# Wi-Fi.net
KiCad netlist of a schematic drawn in Altium Designer
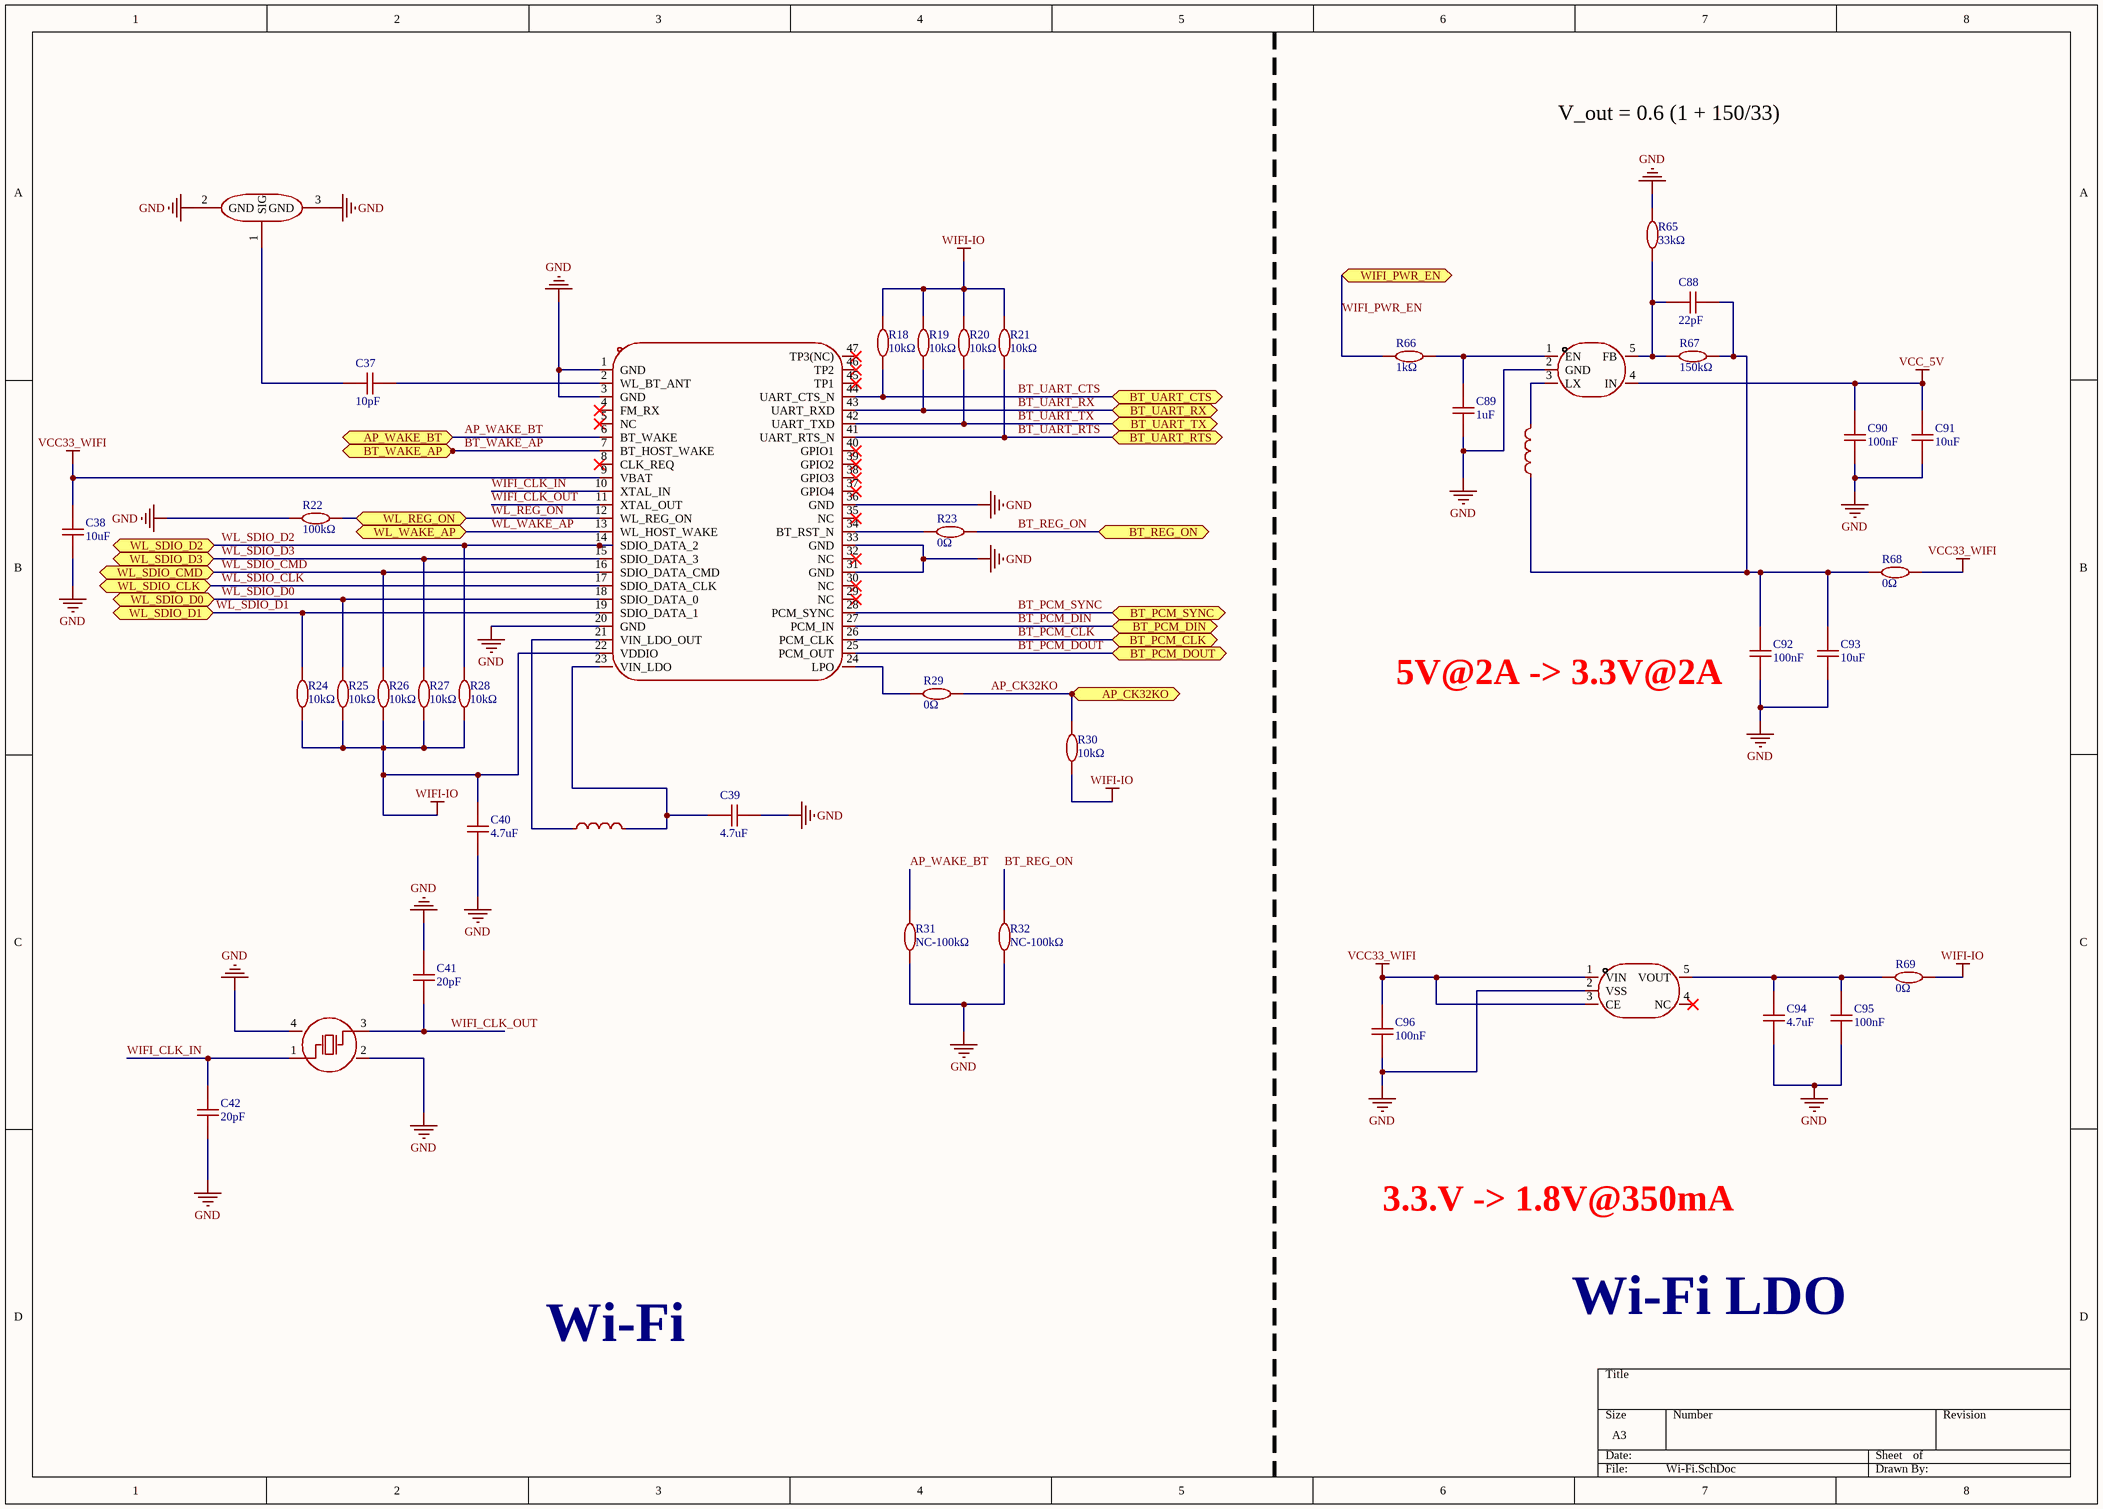
[diagram p0: Wi-Fi.SchDoc]

(export (version "E")
  (design (tool "Eeschema 10.0.6"))
  (components
    (comp (ref "C37")
      (value "10pF")
      (footprint "C0402")
      (description "50V 10pF C0G ±5% 0402 Ceramic Capacitors ROHS")
      (libsource (lib "RLC") (part "10pF"))
    )
    (comp (ref "C38")
      (value "10uF")
      (footprint "C0603")
      (description "10V 10uF X5R ±10% 0603 Ceramic Capacitors ROHS")
      (libsource (lib "RLC") (part "10uF"))
    )
    (comp (ref "C39")
      (value "4.7uF")
      (footprint "C0402")
      (description "10V 4.7uF X5R ±20% 0402 Ceramic Capacitors ROHS")
      (libsource (lib "RLC") (part "4.7uF"))
    )
    (comp (ref "C40")
      (value "4.7uF")
      (footprint "C0402")
      (description "10V 4.7uF X5R ±20% 0402 Ceramic Capacitors ROHS")
      (libsource (lib "RLC") (part "4.7uF"))
    )
    (comp (ref "C41")
      (value "20pF")
      (footprint "C0402")
      (description "50V 20pF NP0 ±5% 0402 Ceramic Capacitors ROHS")
      (libsource (lib "RLC") (part "20pF"))
    )
    (comp (ref "C42")
      (value "20pF")
      (footprint "C0402")
      (description "50V 20pF NP0 ±5% 0402 Ceramic Capacitors ROHS")
      (libsource (lib "RLC") (part "20pF"))
    )
    (comp (ref "C88")
      (value "22pF")
      (footprint "C0402")
      (description "50V 22pF C0G ±5% 0402 Ceramic Capacitors ROHS")
      (libsource (lib "RLC") (part "22pF"))
    )
    (comp (ref "C89")
      (value "1uF")
      (footprint "C0402")
      (description "50V 1uF X5R ±10% 0402 Ceramic Capacitors ROHS")
      (libsource (lib "RLC") (part "1uF"))
    )
    (comp (ref "C90")
      (value "100nF")
      (footprint "C0402")
      (description "50V 100nF X7R ±10% 0402 Ceramic Capacitors ROHS")
      (libsource (lib "RLC") (part "100nF"))
    )
    (comp (ref "C91")
      (value "10uF")
      (footprint "C0603")
      (description "10V 10uF X5R ±10% 0603 Ceramic Capacitors ROHS")
      (libsource (lib "RLC") (part "10uF"))
    )
    (comp (ref "C92")
      (value "100nF")
      (footprint "C0402")
      (description "50V 100nF X7R ±10% 0402 Ceramic Capacitors ROHS")
      (libsource (lib "RLC") (part "100nF"))
    )
    (comp (ref "C93")
      (value "10uF")
      (footprint "C0603")
      (description "10V 10uF X5R ±10% 0603 Ceramic Capacitors ROHS")
      (libsource (lib "RLC") (part "10uF"))
    )
    (comp (ref "C94")
      (value "4.7uF")
      (footprint "C0402")
      (description "10V 4.7uF X5R ±20% 0402 Ceramic Capacitors ROHS")
      (libsource (lib "RLC") (part "4.7uF"))
    )
    (comp (ref "C95")
      (value "100nF")
      (footprint "C0402")
      (description "50V 100nF X7R ±10% 0402 Ceramic Capacitors ROHS")
      (libsource (lib "RLC") (part "100nF"))
    )
    (comp (ref "C96")
      (value "100nF")
      (footprint "C0402")
      (description "50V 100nF X7R ±10% 0402 Ceramic Capacitors ROHS")
      (libsource (lib "RLC") (part "100nF"))
    )
    (comp (ref "JP1")
      (value "6GHz")
      (footprint "RF-SMD_FRF05002-JSS103M")
      (fields (field (name "MANUFACTURER") "HRS(广濑)") (field (name "MANUFACTURER PART") "U.FL-R-SMT-1(80)"))
      (libsource (lib "Connector") (part "U.FL-R-SMT-1(80)_C88374"))
    )
    (comp (ref "L1")
      (value "4.7uH")
      (footprint "IND-SMD_L6.0-W6.0_FNR60XXS")
      (description "2.5A 4.7uH Magnetic Shielded Inductor ±20% 3.6A 75mΩ SMD,6x6mm Fixed Inductors ROHS")
      (fields (field (name "MANUFACTURER") "cjiang(长江微电)") (field (name "MANUFACTURER PART") "FNR6020S4R7MT"))
      (libsource (lib "RLC") (part "FNR6020S4R7MT"))
    )
    (comp (ref "L7")
      (value "4.7uH")
      (footprint "IND-SMD_L6.0-W6.0_FNR60XXS")
      (description "2.5A 4.7uH Magnetic Shielded Inductor ±20% 3.6A 75mΩ SMD,6x6mm Fixed Inductors ROHS")
      (fields (field (name "MANUFACTURER") "cjiang(长江微电)") (field (name "MANUFACTURER PART") "FNR6020S4R7MT"))
      (libsource (lib "RLC") (part "FNR6020S4R7MT"))
    )
    (comp (ref "R18")
      (value "10kΩ")
      (footprint "R0402")
      (description "62.5mW 10kΩ 50V ±100ppm/℃ Thick Film Resistor ±1% 0402 Chip Resistor - Surface Mount ROHS")
      (libsource (lib "RLC") (part "10kΩ"))
    )
    (comp (ref "R19")
      (value "10kΩ")
      (footprint "R0402")
      (description "62.5mW 10kΩ 50V ±100ppm/℃ Thick Film Resistor ±1% 0402 Chip Resistor - Surface Mount ROHS")
      (libsource (lib "RLC") (part "10kΩ"))
    )
    (comp (ref "R20")
      (value "10kΩ")
      (footprint "R0402")
      (description "62.5mW 10kΩ 50V ±100ppm/℃ Thick Film Resistor ±1% 0402 Chip Resistor - Surface Mount ROHS")
      (libsource (lib "RLC") (part "10kΩ"))
    )
    (comp (ref "R21")
      (value "10kΩ")
      (footprint "R0402")
      (description "62.5mW 10kΩ 50V ±100ppm/℃ Thick Film Resistor ±1% 0402 Chip Resistor - Surface Mount ROHS")
      (libsource (lib "RLC") (part "10kΩ"))
    )
    (comp (ref "R22")
      (value "100kΩ")
      (footprint "R0402")
      (description "100kΩ 62.5mW 50V ±100ppm/℃ Thick Film Resistor ±1% 0402 Chip Resistor - Surface Mount ROHS")
      (libsource (lib "RLC") (part "100kΩ"))
    )
    (comp (ref "R23")
      (value "0Ω")
      (footprint "R0402")
      (description "0Ω 62.5mW 50V Thick Film Resistor ±1% 0402 Chip Resistor - Surface Mount ROHS")
      (libsource (lib "RLC") (part "0Ω"))
    )
    (comp (ref "R24")
      (value "10kΩ")
      (footprint "R0402")
      (description "62.5mW 10kΩ 50V ±100ppm/℃ Thick Film Resistor ±1% 0402 Chip Resistor - Surface Mount ROHS")
      (libsource (lib "RLC") (part "10kΩ"))
    )
    (comp (ref "R25")
      (value "10kΩ")
      (footprint "R0402")
      (description "62.5mW 10kΩ 50V ±100ppm/℃ Thick Film Resistor ±1% 0402 Chip Resistor - Surface Mount ROHS")
      (libsource (lib "RLC") (part "10kΩ"))
    )
    (comp (ref "R26")
      (value "10kΩ")
      (footprint "R0402")
      (description "62.5mW 10kΩ 50V ±100ppm/℃ Thick Film Resistor ±1% 0402 Chip Resistor - Surface Mount ROHS")
      (libsource (lib "RLC") (part "10kΩ"))
    )
    (comp (ref "R27")
      (value "10kΩ")
      (footprint "R0402")
      (description "62.5mW 10kΩ 50V ±100ppm/℃ Thick Film Resistor ±1% 0402 Chip Resistor - Surface Mount ROHS")
      (libsource (lib "RLC") (part "10kΩ"))
    )
    (comp (ref "R28")
      (value "10kΩ")
      (footprint "R0402")
      (description "62.5mW 10kΩ 50V ±100ppm/℃ Thick Film Resistor ±1% 0402 Chip Resistor - Surface Mount ROHS")
      (libsource (lib "RLC") (part "10kΩ"))
    )
    (comp (ref "R29")
      (value "0Ω")
      (footprint "R0402")
      (description "0Ω 62.5mW 50V Thick Film Resistor ±1% 0402 Chip Resistor - Surface Mount ROHS")
      (libsource (lib "RLC") (part "0Ω"))
    )
    (comp (ref "R30")
      (value "10kΩ")
      (footprint "R0402")
      (description "62.5mW 10kΩ 50V ±100ppm/℃ Thick Film Resistor ±1% 0402 Chip Resistor - Surface Mount ROHS")
      (libsource (lib "RLC") (part "10kΩ"))
    )
    (comp (ref "R31")
      (value "NC-100kΩ")
      (footprint "R0402")
      (description "100kΩ 62.5mW 50V ±100ppm/℃ Thick Film Resistor ±1% 0402 Chip Resistor - Surface Mount ROHS")
      (libsource (lib "RLC") (part "100kΩ"))
    )
    (comp (ref "R32")
      (value "NC-100kΩ")
      (footprint "R0402")
      (description "100kΩ 62.5mW 50V ±100ppm/℃ Thick Film Resistor ±1% 0402 Chip Resistor - Surface Mount ROHS")
      (libsource (lib "RLC") (part "100kΩ"))
    )
    (comp (ref "R65")
      (value "33kΩ")
      (footprint "R0402")
      (description "62.5mW 33kΩ 50V ±100ppm/℃ Thick Film Resistor ±1% 0402 Chip Resistor - Surface Mount ROHS")
      (libsource (lib "RLC") (part "33kΩ"))
    )
    (comp (ref "R66")
      (value "1kΩ")
      (footprint "R0402")
      (description "1kΩ 62.5mW 50V ±100ppm/℃ Thick Film Resistor ±1% 0402 Chip Resistor - Surface Mount ROHS")
      (libsource (lib "RLC") (part "1kΩ"))
    )
    (comp (ref "R67")
      (value "150kΩ")
      (footprint "R0402")
      (description "62.5mW 150kΩ 50V ±100ppm/℃ Thick Film Resistor ±1% 0402 Chip Resistor - Surface Mount ROHS")
      (libsource (lib "RLC") (part "150kΩ"))
    )
    (comp (ref "R68")
      (value "0Ω")
      (footprint "R0402")
      (description "0Ω 62.5mW 50V Thick Film Resistor ±1% 0402 Chip Resistor - Surface Mount ROHS")
      (libsource (lib "RLC") (part "0Ω"))
    )
    (comp (ref "R69")
      (value "0Ω")
      (footprint "R0402")
      (description "0Ω 62.5mW 50V Thick Film Resistor ±1% 0402 Chip Resistor - Surface Mount ROHS")
      (libsource (lib "RLC") (part "0Ω"))
    )
    (comp (ref "U6")
      (value "2.4GHz")
      (footprint "QFN-44_L12.0-W12.0-P0.90-TL_AP6212")
      (description "2.4GHz -90dBm QFN-44(12x12) RF Transceiver Modules and Modems ROHS")
      (fields (field (name "MANUFACTURER") "AMPAK(正基科技)") (field (name "MANUFACTURER PART") "AP6212"))
      (libsource (lib "IC") (part "AP6212"))
    )
    (comp (ref "U30")
      (value "SY8089A1AAC")
      (footprint "TSOT-23-5_L2.9-W1.6-P0.95-LS2.8-BR")
      (description "1.5MHz Buck 2A Adjustable 1 SOT-23-5 Voltage Regulators - DC DC Switching Regulators ROHS")
      (fields (field (name "MANUFACTURER") "Silergy(矽力杰)"))
      (libsource (lib "LDO") (part "SY8089A1AAC"))
    )
    (comp (ref "U31")
      (value "ME6212C18M5G")
      (footprint "SOT-23-5_L3.0-W1.7-P0.95-LS2.8-BL")
      (fields (field (name "MANUFACTURER") "MICRONE(南京微盟)"))
      (libsource (lib "LDO") (part "ME6212C18M5G"))
    )
    (comp (ref "X1")
      (value "26MHz")
      (footprint "CRYSTAL-SMD_4P-L3.2-W2.5-BL")
      (description "Crystal Oscillator 20pF SMD3225-4P Crystals ROHS")
      (fields (field (name "MANUFACTURER") "YJX(雅晶鑫)") (field (name "MANUFACTURER PART") "TAXM26M4RLBCCT2T"))
      (libsource (lib "OSC") (part "TAXM26M4RLBCCT2T"))
    )
  )
  (nets
    (net (code "1") (name "/AP_CK32KO") (class "Default")
      (node (ref "R29") (pin "2") (pinfunction "2_2") (pintype "passive"))
      (node (ref "R30") (pin "2") (pinfunction "2_2") (pintype "passive"))
    )
    (net (code "2") (name "/AP_WAKE_BT") (class "Default")
      (node (ref "R31") (pin "2") (pinfunction "2_2") (pintype "passive"))
      (node (ref "U6") (pin "6") (pinfunction "BT_WAKE_6") (pintype "passive"))
    )
    (net (code "3") (name "/BT_PCM_CLK") (class "Default")
      (node (ref "U6") (pin "26") (pinfunction "PCM_CLK_26") (pintype "passive"))
    )
    (net (code "4") (name "/BT_PCM_DIN") (class "Default")
      (node (ref "U6") (pin "27") (pinfunction "PCM_IN_27") (pintype "passive"))
    )
    (net (code "5") (name "/BT_PCM_DOUT") (class "Default")
      (node (ref "U6") (pin "25") (pinfunction "PCM_OUT_25") (pintype "passive"))
    )
    (net (code "6") (name "/BT_PCM_SYNC") (class "Default")
      (node (ref "U6") (pin "28") (pinfunction "PCM_SYNC_28") (pintype "passive"))
    )
    (net (code "7") (name "/BT_REG_ON") (class "Default")
      (node (ref "R23") (pin "2") (pinfunction "2_2") (pintype "passive"))
      (node (ref "R32") (pin "2") (pinfunction "2_2") (pintype "passive"))
    )
    (net (code "8") (name "/BT_UART_CTS") (class "Default")
      (node (ref "R18") (pin "1") (pinfunction "1_1") (pintype "passive"))
      (node (ref "U6") (pin "44") (pinfunction "UART_CTS_N_44") (pintype "passive"))
    )
    (net (code "9") (name "/BT_UART_RTS") (class "Default")
      (node (ref "R21") (pin "1") (pinfunction "1_1") (pintype "passive"))
      (node (ref "U6") (pin "41") (pinfunction "UART_RTS_N_41") (pintype "passive"))
    )
    (net (code "10") (name "/BT_UART_RX") (class "Default")
      (node (ref "R19") (pin "1") (pinfunction "1_1") (pintype "passive"))
      (node (ref "U6") (pin "43") (pinfunction "UART_RXD_43") (pintype "passive"))
    )
    (net (code "11") (name "/BT_UART_TX") (class "Default")
      (node (ref "R20") (pin "1") (pinfunction "1_1") (pintype "passive"))
      (node (ref "U6") (pin "42") (pinfunction "UART_TXD_42") (pintype "passive"))
    )
    (net (code "12") (name "/BT_WAKE_AP") (class "Default")
      (node (ref "U6") (pin "7") (pinfunction "BT_HOST_WAKE_7") (pintype "passive"))
    )
    (net (code "13") (name "/WIFI_CLK_IN") (class "Default")
      (node (ref "C42") (pin "2") (pinfunction "2_2") (pintype "passive"))
      (node (ref "U6") (pin "10") (pinfunction "XTAL_IN_10") (pintype "passive"))
      (node (ref "X1") (pin "1") (pinfunction "OSC1_1") (pintype "passive"))
    )
    (net (code "14") (name "/WIFI_CLK_OUT") (class "Default")
      (node (ref "C41") (pin "1") (pinfunction "1_1") (pintype "passive"))
      (node (ref "U6") (pin "11") (pinfunction "XTAL_OUT_11") (pintype "passive"))
      (node (ref "X1") (pin "3") (pinfunction "OSC2_3") (pintype "passive"))
    )
    (net (code "15") (name "/WIFI_PWR_EN") (class "Default")
      (node (ref "R66") (pin "1") (pinfunction "1_1") (pintype "passive"))
    )
    (net (code "16") (name "/WL_REG_ON") (class "Default")
      (node (ref "R22") (pin "2") (pinfunction "2_2") (pintype "passive"))
      (node (ref "U6") (pin "12") (pinfunction "WL_REG_ON_12") (pintype "passive"))
    )
    (net (code "17") (name "/WL_SDIO_CLK") (class "Default")
      (node (ref "U6") (pin "17") (pinfunction "SDIO_DATA_CLK_17") (pintype "passive"))
    )
    (net (code "18") (name "/WL_SDIO_CMD") (class "Default")
      (node (ref "R26") (pin "2") (pinfunction "2_2") (pintype "passive"))
      (node (ref "U6") (pin "16") (pinfunction "SDIO_DATA_CMD_16") (pintype "passive"))
    )
    (net (code "19") (name "/WL_SDIO_D0") (class "Default")
      (node (ref "R25") (pin "2") (pinfunction "2_2") (pintype "passive"))
      (node (ref "U6") (pin "18") (pinfunction "SDIO_DATA_0_18") (pintype "passive"))
    )
    (net (code "20") (name "/WL_SDIO_D1") (class "Default")
      (node (ref "R24") (pin "2") (pinfunction "2_2") (pintype "passive"))
      (node (ref "U6") (pin "19") (pinfunction "SDIO_DATA_1_19") (pintype "passive"))
    )
    (net (code "21") (name "/WL_SDIO_D2") (class "Default")
      (node (ref "R28") (pin "2") (pinfunction "2_2") (pintype "passive"))
      (node (ref "U6") (pin "14") (pinfunction "SDIO_DATA_2_14") (pintype "passive"))
    )
    (net (code "22") (name "/WL_SDIO_D3") (class "Default")
      (node (ref "R27") (pin "2") (pinfunction "2_2") (pintype "passive"))
      (node (ref "U6") (pin "15") (pinfunction "SDIO_DATA_3_15") (pintype "passive"))
    )
    (net (code "23") (name "/WL_WAKE_AP") (class "Default")
      (node (ref "U6") (pin "13") (pinfunction "WL_HOST_WAKE_13") (pintype "passive"))
    )
    (net (code "24") (name "GND") (class "Default")
      (node (ref "C38") (pin "1") (pinfunction "1_1") (pintype "passive"))
      (node (ref "C39") (pin "2") (pinfunction "2_2") (pintype "passive"))
      (node (ref "C40") (pin "1") (pinfunction "1_1") (pintype "passive"))
      (node (ref "C41") (pin "2") (pinfunction "2_2") (pintype "passive"))
      (node (ref "C42") (pin "1") (pinfunction "1_1") (pintype "passive"))
      (node (ref "C89") (pin "1") (pinfunction "1_1") (pintype "passive"))
      (node (ref "C90") (pin "1") (pinfunction "1_1") (pintype "passive"))
      (node (ref "C91") (pin "1") (pinfunction "1_1") (pintype "passive"))
      (node (ref "C92") (pin "1") (pinfunction "1_1") (pintype "passive"))
      (node (ref "C93") (pin "1") (pinfunction "1_1") (pintype "passive"))
      (node (ref "C94") (pin "1") (pinfunction "1_1") (pintype "passive"))
      (node (ref "C95") (pin "1") (pinfunction "1_1") (pintype "passive"))
      (node (ref "C96") (pin "1") (pinfunction "1_1") (pintype "passive"))
      (node (ref "JP1") (pin "2") (pinfunction "GND_2") (pintype "passive"))
      (node (ref "JP1") (pin "3") (pinfunction "GND_3") (pintype "passive"))
      (node (ref "R22") (pin "1") (pinfunction "1_1") (pintype "passive"))
      (node (ref "R31") (pin "1") (pinfunction "1_1") (pintype "passive"))
      (node (ref "R32") (pin "1") (pinfunction "1_1") (pintype "passive"))
      (node (ref "R65") (pin "2") (pinfunction "2_2") (pintype "passive"))
      (node (ref "U30") (pin "2") (pinfunction "GND_2") (pintype "passive"))
      (node (ref "U31") (pin "2") (pinfunction "VSS_2") (pintype "passive"))
      (node (ref "U6") (pin "1") (pinfunction "GND_1") (pintype "passive"))
      (node (ref "U6") (pin "20") (pinfunction "GND_20") (pintype "passive"))
      (node (ref "U6") (pin "3") (pinfunction "GND_3") (pintype "passive"))
      (node (ref "U6") (pin "31") (pinfunction "GND_31") (pintype "passive"))
      (node (ref "U6") (pin "33") (pinfunction "GND_33") (pintype "passive"))
      (node (ref "U6") (pin "36") (pinfunction "GND_36") (pintype "passive"))
      (node (ref "X1") (pin "2") (pinfunction "GND_2") (pintype "passive"))
      (node (ref "X1") (pin "4") (pinfunction "GND_4") (pintype "passive"))
    )
    (net (code "25") (name "Net-(C88-Pad2)") (class "Default")
      (node (ref "C88") (pin "2") (pinfunction "2_2") (pintype "passive"))
      (node (ref "C92") (pin "2") (pinfunction "2_2") (pintype "passive"))
      (node (ref "C93") (pin "2") (pinfunction "2_2") (pintype "passive"))
      (node (ref "L7") (pin "1") (pinfunction "1_1") (pintype "passive"))
      (node (ref "R67") (pin "2") (pinfunction "2_2") (pintype "passive"))
      (node (ref "R68") (pin "1") (pinfunction "1_1") (pintype "passive"))
    )
    (net (code "26") (name "Net-(JP1-SIG)") (class "Default")
      (node (ref "C37") (pin "1") (pinfunction "1_1") (pintype "passive"))
      (node (ref "JP1") (pin "1") (pinfunction "SIG_1") (pintype "passive"))
    )
    (net (code "27") (name "Net-(U6-BT_RST_N)") (class "Default")
      (node (ref "R23") (pin "1") (pinfunction "1_1") (pintype "passive"))
      (node (ref "U6") (pin "34") (pinfunction "BT_RST_N_34") (pintype "passive"))
    )
    (net (code "28") (name "Net-(U6-LPO)") (class "Default")
      (node (ref "R29") (pin "1") (pinfunction "1_1") (pintype "passive"))
      (node (ref "U6") (pin "24") (pinfunction "LPO_24") (pintype "passive"))
    )
    (net (code "29") (name "Net-(U6-VIN_LDO)") (class "Default")
      (node (ref "C39") (pin "1") (pinfunction "1_1") (pintype "passive"))
      (node (ref "L1") (pin "2") (pinfunction "2_2") (pintype "passive"))
      (node (ref "U6") (pin "23") (pinfunction "VIN_LDO_23") (pintype "passive"))
    )
    (net (code "30") (name "Net-(U6-VIN_LDO_OUT)") (class "Default")
      (node (ref "L1") (pin "1") (pinfunction "1_1") (pintype "passive"))
      (node (ref "U6") (pin "21") (pinfunction "VIN_LDO_OUT_21") (pintype "passive"))
    )
    (net (code "31") (name "Net-(U6-WL_BT_ANT)") (class "Default")
      (node (ref "C37") (pin "2") (pinfunction "2_2") (pintype "passive"))
      (node (ref "U6") (pin "2") (pinfunction "WL_BT_ANT_2") (pintype "passive"))
    )
    (net (code "32") (name "Net-(U30-EN)") (class "Default")
      (node (ref "C89") (pin "2") (pinfunction "2_2") (pintype "passive"))
      (node (ref "R66") (pin "2") (pinfunction "2_2") (pintype "passive"))
      (node (ref "U30") (pin "1") (pinfunction "EN_1") (pintype "passive"))
    )
    (net (code "33") (name "Net-(U30-FB)") (class "Default")
      (node (ref "C88") (pin "1") (pinfunction "1_1") (pintype "passive"))
      (node (ref "R65") (pin "1") (pinfunction "1_1") (pintype "passive"))
      (node (ref "R67") (pin "1") (pinfunction "1_1") (pintype "passive"))
      (node (ref "U30") (pin "5") (pinfunction "FB_5") (pintype "passive"))
    )
    (net (code "34") (name "Net-(U30-LX)") (class "Default")
      (node (ref "L7") (pin "2") (pinfunction "2_2") (pintype "passive"))
      (node (ref "U30") (pin "3") (pinfunction "LX_3") (pintype "passive"))
    )
    (net (code "35") (name "Net-(U31-VOUT)") (class "Default")
      (node (ref "C94") (pin "2") (pinfunction "2_2") (pintype "passive"))
      (node (ref "C95") (pin "2") (pinfunction "2_2") (pintype "passive"))
      (node (ref "R69") (pin "1") (pinfunction "1_1") (pintype "passive"))
      (node (ref "U31") (pin "5") (pinfunction "VOUT_5") (pintype "passive"))
    )
    (net (code "36") (name "VCC33_WIFI") (class "Default")
      (node (ref "C38") (pin "2") (pinfunction "2_2") (pintype "passive"))
      (node (ref "C96") (pin "2") (pinfunction "2_2") (pintype "passive"))
      (node (ref "R68") (pin "2") (pinfunction "2_2") (pintype "passive"))
      (node (ref "U31") (pin "1") (pinfunction "VIN_1") (pintype "passive"))
      (node (ref "U31") (pin "3") (pinfunction "CE_3") (pintype "passive"))
      (node (ref "U6") (pin "9") (pinfunction "VBAT_9") (pintype "passive"))
    )
    (net (code "37") (name "VCC_5V") (class "Default")
      (node (ref "C90") (pin "2") (pinfunction "2_2") (pintype "passive"))
      (node (ref "C91") (pin "2") (pinfunction "2_2") (pintype "passive"))
      (node (ref "U30") (pin "4") (pinfunction "IN_4") (pintype "passive"))
    )
    (net (code "38") (name "WIFI-IO") (class "Default")
      (node (ref "C40") (pin "2") (pinfunction "2_2") (pintype "passive"))
      (node (ref "R18") (pin "2") (pinfunction "2_2") (pintype "passive"))
      (node (ref "R19") (pin "2") (pinfunction "2_2") (pintype "passive"))
      (node (ref "R20") (pin "2") (pinfunction "2_2") (pintype "passive"))
      (node (ref "R21") (pin "2") (pinfunction "2_2") (pintype "passive"))
      (node (ref "R24") (pin "1") (pinfunction "1_1") (pintype "passive"))
      (node (ref "R25") (pin "1") (pinfunction "1_1") (pintype "passive"))
      (node (ref "R26") (pin "1") (pinfunction "1_1") (pintype "passive"))
      (node (ref "R27") (pin "1") (pinfunction "1_1") (pintype "passive"))
      (node (ref "R28") (pin "1") (pinfunction "1_1") (pintype "passive"))
      (node (ref "R30") (pin "1") (pinfunction "1_1") (pintype "passive"))
      (node (ref "R69") (pin "2") (pinfunction "2_2") (pintype "passive"))
      (node (ref "U6") (pin "22") (pinfunction "VDDIO_22") (pintype "passive"))
    )
    (net (code "39") (name "unconnected-(U6-CLK_REQ-Pad8)") (class "Default")
      (node (ref "U6") (pin "8") (pinfunction "CLK_REQ_8") (pintype "passive+no_connect"))
    )
    (net (code "40") (name "unconnected-(U6-FM_RX-Pad4)") (class "Default")
      (node (ref "U6") (pin "4") (pinfunction "FM_RX_4") (pintype "passive+no_connect"))
    )
    (net (code "41") (name "unconnected-(U6-GPIO1-Pad40)") (class "Default")
      (node (ref "U6") (pin "40") (pinfunction "GPIO1_40") (pintype "passive+no_connect"))
    )
    (net (code "42") (name "unconnected-(U6-GPIO2-Pad39)") (class "Default")
      (node (ref "U6") (pin "39") (pinfunction "GPIO2_39") (pintype "passive+no_connect"))
    )
    (net (code "43") (name "unconnected-(U6-GPIO3-Pad38)") (class "Default")
      (node (ref "U6") (pin "38") (pinfunction "GPIO3_38") (pintype "passive+no_connect"))
    )
    (net (code "44") (name "unconnected-(U6-GPIO4-Pad37)") (class "Default")
      (node (ref "U6") (pin "37") (pinfunction "GPIO4_37") (pintype "passive+no_connect"))
    )
    (net (code "45") (name "unconnected-(U6-NC-Pad5)") (class "Default")
      (node (ref "U6") (pin "5") (pinfunction "NC_5") (pintype "passive+no_connect"))
    )
    (net (code "46") (name "unconnected-(U6-NC-Pad29)") (class "Default")
      (node (ref "U6") (pin "29") (pinfunction "NC_29") (pintype "passive+no_connect"))
    )
    (net (code "47") (name "unconnected-(U6-NC-Pad30)") (class "Default")
      (node (ref "U6") (pin "30") (pinfunction "NC_30") (pintype "passive+no_connect"))
    )
    (net (code "48") (name "unconnected-(U6-NC-Pad32)") (class "Default")
      (node (ref "U6") (pin "32") (pinfunction "NC_32") (pintype "passive+no_connect"))
    )
    (net (code "49") (name "unconnected-(U6-NC-Pad35)") (class "Default")
      (node (ref "U6") (pin "35") (pinfunction "NC_35") (pintype "passive+no_connect"))
    )
    (net (code "50") (name "unconnected-(U6-TP1-Pad45)") (class "Default")
      (node (ref "U6") (pin "45") (pinfunction "TP1_45") (pintype "passive+no_connect"))
    )
    (net (code "51") (name "unconnected-(U6-TP2-Pad46)") (class "Default")
      (node (ref "U6") (pin "46") (pinfunction "TP2_46") (pintype "passive+no_connect"))
    )
    (net (code "52") (name "unconnected-(U6-TP3(NC)-Pad47)") (class "Default")
      (node (ref "U6") (pin "47") (pinfunction "TP3(NC)_47") (pintype "passive+no_connect"))
    )
    (net (code "53") (name "unconnected-(U31-NC-Pad4)") (class "Default")
      (node (ref "U31") (pin "4") (pinfunction "NC_4") (pintype "passive+no_connect"))
    )
  )
)
